# TPA2.net
KiCad netlist of a schematic drawn in Altium Designer
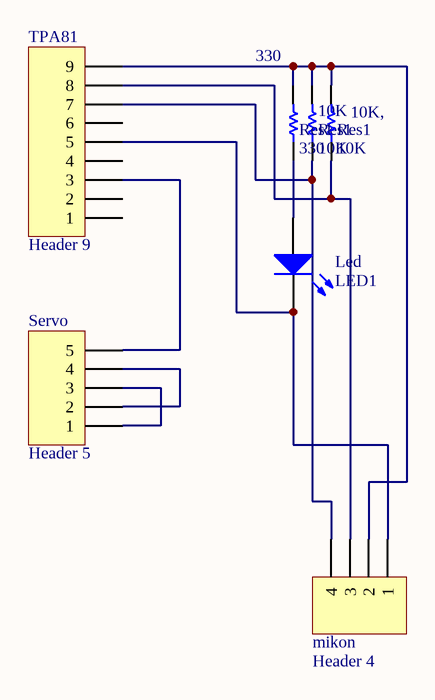
[diagram p0: TPA2.SchDoc]

(export (version "E")
  (design (tool "Eeschema 10.0.6"))
  (components
    (comp (ref "10K")
      (value "Res1")
      (footprint "AXIAL-0.3")
      (description "Resistor")
      (fields (field (name "ALTIUM_VALUE") "10K") (field (name "PUBLISHER") "Altium Limited"))
      (libsource (lib "Miscellaneous Devices") (part "Res1"))
    )
    (comp (ref "10K,")
      (value "Res1")
      (footprint "AXIAL-0.3")
      (description "Resistor")
      (fields (field (name "ALTIUM_VALUE") "10K") (field (name "PUBLISHER") "Altium Limited"))
      (libsource (lib "Miscellaneous Devices") (part "Res1"))
    )
    (comp (ref "330")
      (value "Res1")
      (footprint "AXIAL-0.3")
      (description "Resistor")
      (fields (field (name "ALTIUM_VALUE") "330") (field (name "PUBLISHER") "Altium Limited"))
      (libsource (lib "Miscellaneous Devices") (part "Res1"))
    )
    (comp (ref "Led")
      (value "LED1")
      (footprint "LED-1")
      (description "Typical RED GaAs LED")
      (fields (field (name "PUBLISHER") "Altium Limited"))
      (libsource (lib "Miscellaneous Devices") (part "LED1"))
    )
    (comp (ref "mikon")
      (value "Header 4")
      (footprint "HDR1X4")
      (description "Header, 4-Pin")
      (fields (field (name "PUBLISHER") "Altium Limited"))
      (libsource (lib "Miscellaneous Connectors") (part "Header 4"))
    )
    (comp (ref "Servo")
      (value "Header 5")
      (footprint "HDR1X5")
      (description "Header, 5-Pin")
      (fields (field (name "PUBLISHER") "Altium Limited"))
      (libsource (lib "Miscellaneous Connectors") (part "Header 5"))
    )
    (comp (ref "TPA81")
      (value "Header 9")
      (footprint "HDR1X9")
      (description "Header, 9-Pin")
      (fields (field (name "PUBLISHER") "Altium Limited"))
      (libsource (lib "Miscellaneous Connectors") (part "Header 9"))
    )
  )
  (nets
    (net (code "1") (name "Net-(10K,-Pad1)") (class "Default")
      (node (ref "10K,") (pin "1") (pinfunction "1_1") (pintype "passive"))
      (node (ref "TPA81") (pin "8") (pinfunction "8_8") (pintype "passive"))
      (node (ref "mikon") (pin "3") (pinfunction "3_3") (pintype "passive"))
    )
    (net (code "2") (name "Net-(10K,-Pad2)") (class "Default")
      (node (ref "10K") (pin "2") (pinfunction "2_2") (pintype "passive"))
      (node (ref "10K,") (pin "2") (pinfunction "2_2") (pintype "passive"))
      (node (ref "330") (pin "2") (pinfunction "2_2") (pintype "passive"))
      (node (ref "TPA81") (pin "9") (pinfunction "9_9") (pintype "passive"))
      (node (ref "mikon") (pin "2") (pinfunction "2_2") (pintype "passive"))
    )
    (net (code "3") (name "Net-(10K-Pad1)") (class "Default")
      (node (ref "10K") (pin "1") (pinfunction "1_1") (pintype "passive"))
      (node (ref "TPA81") (pin "7") (pinfunction "7_7") (pintype "passive"))
      (node (ref "mikon") (pin "4") (pinfunction "4_4") (pintype "passive"))
    )
    (net (code "4") (name "Net-(Led-A)") (class "Default")
      (node (ref "330") (pin "1") (pinfunction "1_1") (pintype "passive"))
      (node (ref "Led") (pin "1") (pinfunction "A_1") (pintype "passive"))
    )
    (net (code "5") (name "Net-(Led-K)") (class "Default")
      (node (ref "Led") (pin "2") (pinfunction "K_2") (pintype "passive"))
      (node (ref "TPA81") (pin "5") (pinfunction "5_5") (pintype "passive"))
      (node (ref "mikon") (pin "1") (pinfunction "1_1") (pintype "passive"))
    )
    (net (code "6") (name "Net-(Servo-Pad1)") (class "Default")
      (node (ref "Servo") (pin "1") (pinfunction "1_1") (pintype "passive"))
      (node (ref "Servo") (pin "3") (pinfunction "3_3") (pintype "passive"))
    )
    (net (code "7") (name "Net-(Servo-Pad2)") (class "Default")
      (node (ref "Servo") (pin "2") (pinfunction "2_2") (pintype "passive"))
      (node (ref "Servo") (pin "4") (pinfunction "4_4") (pintype "passive"))
    )
    (net (code "8") (name "Net-(Servo-Pad5)") (class "Default")
      (node (ref "Servo") (pin "5") (pinfunction "5_5") (pintype "passive"))
      (node (ref "TPA81") (pin "3") (pinfunction "3_3") (pintype "passive"))
    )
    (net (code "9") (name "unconnected-(TPA81-Pad1)") (class "Default")
      (node (ref "TPA81") (pin "1") (pinfunction "1_1") (pintype "passive"))
    )
    (net (code "10") (name "unconnected-(TPA81-Pad2)") (class "Default")
      (node (ref "TPA81") (pin "2") (pinfunction "2_2") (pintype "passive"))
    )
    (net (code "11") (name "unconnected-(TPA81-Pad4)") (class "Default")
      (node (ref "TPA81") (pin "4") (pinfunction "4_4") (pintype "passive"))
    )
    (net (code "12") (name "unconnected-(TPA81-Pad6)") (class "Default")
      (node (ref "TPA81") (pin "6") (pinfunction "6_6") (pintype "passive"))
    )
  )
)
